# keg-vol-weight-mon.net
KiCad netlist of a schematic drawn in EAGLE
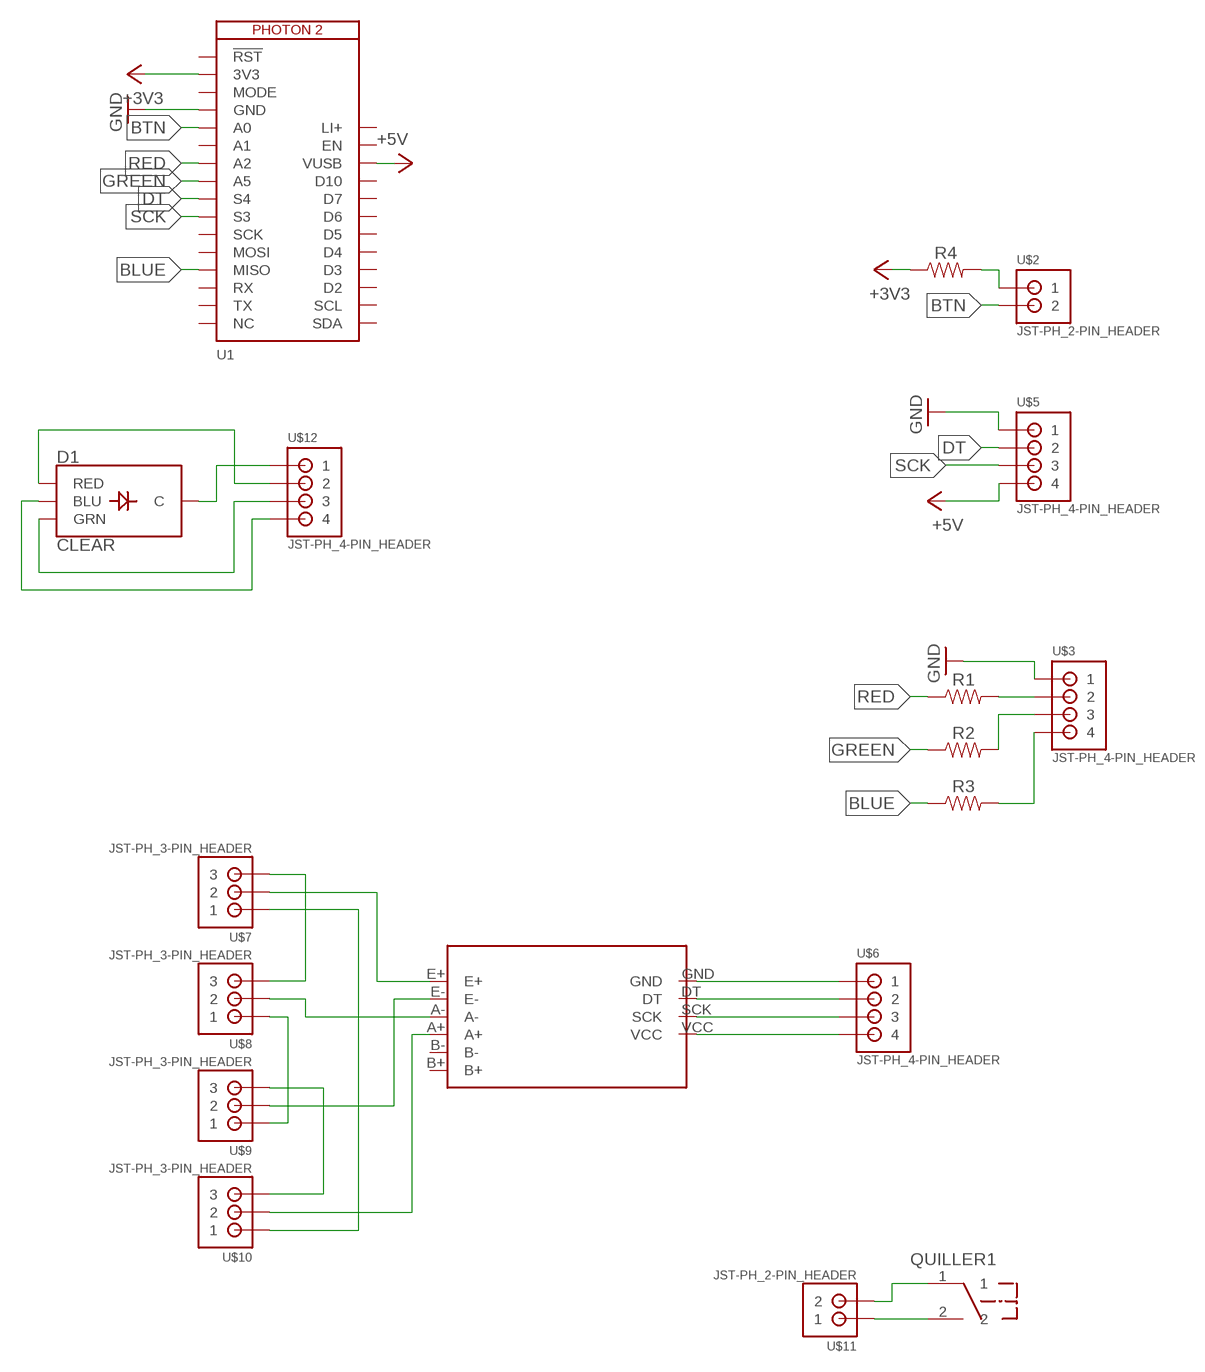
[diagram p0: schematic, sheet 1]

(export (version "E")
  (design (tool "Eeschema 10.0.6"))
  (components
    (comp (ref "D1")
      (value "CLEAR")
      (footprint "eagle-import:LED-RGB-THRU")
      (libsource (lib "eagle-import") (part "LED-RGB-CCCLEAR"))
    )
    (comp (ref "QUILLER1")
      (value "6MM-2PIN-TAC-MOM-SWITCH")
      (footprint "eagle-import:6MM-2PIN-TAC-MOM-SWITCH")
      (libsource (lib "eagle-import") (part "6MM-2PIN-TAC-MOM-SWITCH"))
    )
    (comp (ref "R1")
      (value "RESISTORAXIAL-0.3")
      (footprint "eagle-import:AXIAL-0.3")
      (libsource (lib "eagle-import") (part "RESISTORAXIAL-0.3"))
    )
    (comp (ref "R2")
      (value "RESISTORAXIAL-0.3")
      (footprint "eagle-import:AXIAL-0.3")
      (libsource (lib "eagle-import") (part "RESISTORAXIAL-0.3"))
    )
    (comp (ref "R3")
      (value "RESISTORAXIAL-0.3")
      (footprint "eagle-import:AXIAL-0.3")
      (libsource (lib "eagle-import") (part "RESISTORAXIAL-0.3"))
    )
    (comp (ref "R4")
      (value "RESISTORAXIAL-0.3")
      (footprint "eagle-import:AXIAL-0.3")
      (libsource (lib "eagle-import") (part "RESISTORAXIAL-0.3"))
    )
    (comp (ref "U$2")
      (value "JST-PH_2-PIN_HEADER")
      (footprint "eagle-import:JST_B2B-PH_HEADER")
      (libsource (lib "eagle-import") (part "JST-PH_2-PIN_HEADER"))
    )
    (comp (ref "U$3")
      (value "JST-PH_4-PIN_HEADER")
      (footprint "eagle-import:JST_B4B-PH_HEADER")
      (libsource (lib "eagle-import") (part "JST-PH_4-PIN_HEADER"))
    )
    (comp (ref "U$4")
      (value "HX711A")
      (footprint "eagle-import:HX711")
      (libsource (lib "eagle-import") (part "HX711A"))
    )
    (comp (ref "U$5")
      (value "JST-PH_4-PIN_HEADER")
      (footprint "eagle-import:JST_B4B-PH_HEADER")
      (libsource (lib "eagle-import") (part "JST-PH_4-PIN_HEADER"))
    )
    (comp (ref "U$6")
      (value "JST-PH_4-PIN_HEADER")
      (footprint "eagle-import:JST_B4B-PH_HEADER")
      (libsource (lib "eagle-import") (part "JST-PH_4-PIN_HEADER"))
    )
    (comp (ref "U$7")
      (value "JST-PH_3-PIN_HEADER")
      (footprint "eagle-import:JST_B3B-PH_HEADER")
      (libsource (lib "eagle-import") (part "JST-PH_3-PIN_HEADER"))
    )
    (comp (ref "U$8")
      (value "JST-PH_3-PIN_HEADER")
      (footprint "eagle-import:JST_B3B-PH_HEADER")
      (libsource (lib "eagle-import") (part "JST-PH_3-PIN_HEADER"))
    )
    (comp (ref "U$9")
      (value "JST-PH_3-PIN_HEADER")
      (footprint "eagle-import:JST_B3B-PH_HEADER")
      (libsource (lib "eagle-import") (part "JST-PH_3-PIN_HEADER"))
    )
    (comp (ref "U$10")
      (value "JST-PH_3-PIN_HEADER")
      (footprint "eagle-import:JST_B3B-PH_HEADER")
      (libsource (lib "eagle-import") (part "JST-PH_3-PIN_HEADER"))
    )
    (comp (ref "U$11")
      (value "JST-PH_2-PIN_HEADER")
      (footprint "eagle-import:JST_B2B-PH_HEADER")
      (libsource (lib "eagle-import") (part "JST-PH_2-PIN_HEADER"))
    )
    (comp (ref "U$12")
      (value "JST-PH_4-PIN_HEADER")
      (footprint "eagle-import:JST_B4B-PH_HEADER")
      (libsource (lib "eagle-import") (part "JST-PH_4-PIN_HEADER"))
    )
    (comp (ref "U1")
      (value "PHOTON2")
      (footprint "eagle-import:PHOTON2")
      (libsource (lib "eagle-import") (part "PHOTON2"))
    )
  )
  (nets
    (net (code "1") (name "+3V3") (class "Default")
      (node (ref "R4") (pin "P$1") (pinfunction "1_P$1") (pintype "passive"))
      (node (ref "U1") (pin "2") (pinfunction "3V3_2") (pintype "power_in"))
    )
    (net (code "2") (name "+5V") (class "Default")
      (node (ref "U$5") (pin "P4") (pinfunction "4_P4") (pintype "bidirectional"))
      (node (ref "U1") (pin "26") (pinfunction "VUSB_26") (pintype "power_in"))
    )
    (net (code "3") (name "/LI+") (class "Default")
      (node (ref "U1") (pin "28") (pinfunction "LI+_28") (pintype "power_in"))
    )
    (net (code "4") (name "BLUE") (class "Default")
      (node (ref "R3") (pin "P$1") (pinfunction "1_P$1") (pintype "passive"))
      (node (ref "U1") (pin "13") (pinfunction "MISO_13") (pintype "bidirectional"))
    )
    (net (code "5") (name "BTN") (class "Default")
      (node (ref "U$2") (pin "P2") (pinfunction "2_P2") (pintype "bidirectional"))
      (node (ref "U1") (pin "5") (pinfunction "A0_5") (pintype "bidirectional"))
    )
    (net (code "6") (name "DT") (class "Default")
      (node (ref "U$5") (pin "P2") (pinfunction "2_P2") (pintype "bidirectional"))
      (node (ref "U1") (pin "9") (pinfunction "S4_9") (pintype "bidirectional"))
    )
    (net (code "7") (name "GND") (class "Default")
      (node (ref "U$3") (pin "P1") (pinfunction "1_P1") (pintype "bidirectional"))
      (node (ref "U$5") (pin "P1") (pinfunction "1_P1") (pintype "bidirectional"))
      (node (ref "U1") (pin "4") (pinfunction "GND_4") (pintype "power_in"))
    )
    (net (code "8") (name "GREEN") (class "Default")
      (node (ref "R2") (pin "P$1") (pinfunction "1_P$1") (pintype "passive"))
      (node (ref "U1") (pin "8") (pinfunction "A5_8") (pintype "bidirectional"))
    )
    (net (code "9") (name "Net-(D1-BLU)") (class "Default")
      (node (ref "D1") (pin "4") (pinfunction "BLU_4") (pintype "bidirectional"))
      (node (ref "U$12") (pin "P4") (pinfunction "4_P4") (pintype "bidirectional"))
    )
    (net (code "10") (name "Net-(D1-C)") (class "Default")
      (node (ref "D1") (pin "2") (pinfunction "C_2") (pintype "bidirectional"))
      (node (ref "U$12") (pin "P1") (pinfunction "1_P1") (pintype "bidirectional"))
    )
    (net (code "11") (name "Net-(D1-GRN)") (class "Default")
      (node (ref "D1") (pin "3") (pinfunction "GRN_3") (pintype "bidirectional"))
      (node (ref "U$12") (pin "P3") (pinfunction "3_P3") (pintype "bidirectional"))
    )
    (net (code "12") (name "Net-(D1-RED)") (class "Default")
      (node (ref "D1") (pin "1") (pinfunction "RED_1") (pintype "bidirectional"))
      (node (ref "U$12") (pin "P2") (pinfunction "2_P2") (pintype "bidirectional"))
    )
    (net (code "13") (name "Net-(R1-2)") (class "Default")
      (node (ref "R1") (pin "P$2") (pinfunction "2_P$2") (pintype "passive"))
      (node (ref "U$3") (pin "P2") (pinfunction "2_P2") (pintype "bidirectional"))
    )
    (net (code "14") (name "Net-(R2-2)") (class "Default")
      (node (ref "R2") (pin "P$2") (pinfunction "2_P$2") (pintype "passive"))
      (node (ref "U$3") (pin "P3") (pinfunction "3_P3") (pintype "bidirectional"))
    )
    (net (code "15") (name "Net-(R3-2)") (class "Default")
      (node (ref "R3") (pin "P$2") (pinfunction "2_P$2") (pintype "passive"))
      (node (ref "U$3") (pin "P4") (pinfunction "4_P4") (pintype "bidirectional"))
    )
    (net (code "16") (name "Net-(R4-2)") (class "Default")
      (node (ref "R4") (pin "P$2") (pinfunction "2_P$2") (pintype "passive"))
      (node (ref "U$2") (pin "P1") (pinfunction "1_P1") (pintype "bidirectional"))
    )
    (net (code "17") (name "Net-(U$6-1)") (class "Default")
      (node (ref "U$4") (pin "GND") (pinfunction "GND_GND") (pintype "bidirectional"))
      (node (ref "U$6") (pin "P1") (pinfunction "1_P1") (pintype "bidirectional"))
    )
    (net (code "18") (name "Net-(U$6-2)") (class "Default")
      (node (ref "U$4") (pin "DT") (pinfunction "DT_DT") (pintype "bidirectional"))
      (node (ref "U$6") (pin "P2") (pinfunction "2_P2") (pintype "bidirectional"))
    )
    (net (code "19") (name "Net-(U$6-3)") (class "Default")
      (node (ref "U$4") (pin "SCK") (pinfunction "SCK_SCK") (pintype "bidirectional"))
      (node (ref "U$6") (pin "P3") (pinfunction "3_P3") (pintype "bidirectional"))
    )
    (net (code "20") (name "Net-(U$6-4)") (class "Default")
      (node (ref "U$4") (pin "VCC") (pinfunction "VCC_VCC") (pintype "bidirectional"))
      (node (ref "U$6") (pin "P4") (pinfunction "4_P4") (pintype "bidirectional"))
    )
    (net (code "21") (name "Net-(U$7-2)") (class "Default")
      (node (ref "U$4") (pin "E+") (pinfunction "E+_E+") (pintype "bidirectional"))
      (node (ref "U$7") (pin "P2") (pinfunction "2_P2") (pintype "bidirectional"))
    )
    (net (code "22") (name "Net-(U$7-3)") (class "Default")
      (node (ref "U$7") (pin "P3") (pinfunction "3_P3") (pintype "bidirectional"))
      (node (ref "U$8") (pin "P3") (pinfunction "3_P3") (pintype "bidirectional"))
    )
    (net (code "23") (name "Net-(U$8-1)") (class "Default")
      (node (ref "U$8") (pin "P1") (pinfunction "1_P1") (pintype "bidirectional"))
      (node (ref "U$9") (pin "P1") (pinfunction "1_P1") (pintype "bidirectional"))
    )
    (net (code "24") (name "Net-(U$8-2)") (class "Default")
      (node (ref "U$4") (pin "A-") (pinfunction "A-_A-") (pintype "bidirectional"))
      (node (ref "U$8") (pin "P2") (pinfunction "2_P2") (pintype "bidirectional"))
    )
    (net (code "25") (name "Net-(U$9-2)") (class "Default")
      (node (ref "U$4") (pin "E-") (pinfunction "E-_E-") (pintype "bidirectional"))
      (node (ref "U$9") (pin "P2") (pinfunction "2_P2") (pintype "bidirectional"))
    )
    (net (code "26") (name "Net-(U$10-1)") (class "Default")
      (node (ref "U$10") (pin "P1") (pinfunction "1_P1") (pintype "bidirectional"))
      (node (ref "U$7") (pin "P1") (pinfunction "1_P1") (pintype "bidirectional"))
    )
    (net (code "27") (name "Net-(U$10-2)") (class "Default")
      (node (ref "U$10") (pin "P2") (pinfunction "2_P2") (pintype "bidirectional"))
      (node (ref "U$4") (pin "A+") (pinfunction "A+_A+") (pintype "bidirectional"))
    )
    (net (code "28") (name "Net-(U$10-3)") (class "Default")
      (node (ref "U$10") (pin "P3") (pinfunction "3_P3") (pintype "bidirectional"))
      (node (ref "U$9") (pin "P3") (pinfunction "3_P3") (pintype "bidirectional"))
    )
    (net (code "29") (name "Net-(U$11-1)") (class "Default")
      (node (ref "QUILLER1") (pin "2") (pinfunction "2_2") (pintype "bidirectional"))
      (node (ref "U$11") (pin "P1") (pinfunction "1_P1") (pintype "bidirectional"))
    )
    (net (code "30") (name "Net-(U$11-2)") (class "Default")
      (node (ref "QUILLER1") (pin "1") (pinfunction "1_1") (pintype "bidirectional"))
      (node (ref "U$11") (pin "P2") (pinfunction "2_P2") (pintype "bidirectional"))
    )
    (net (code "31") (name "RED") (class "Default")
      (node (ref "R1") (pin "P$1") (pinfunction "1_P$1") (pintype "passive"))
      (node (ref "U1") (pin "7") (pinfunction "A2_7") (pintype "bidirectional"))
    )
    (net (code "32") (name "SCK") (class "Default")
      (node (ref "U$5") (pin "P3") (pinfunction "3_P3") (pintype "bidirectional"))
      (node (ref "U1") (pin "10") (pinfunction "S3_10") (pintype "bidirectional"))
    )
    (net (code "33") (name "unconnected-(U$4-PadB+)") (class "Default")
      (node (ref "U$4") (pin "B+") (pinfunction "B+_B+") (pintype "bidirectional"))
    )
    (net (code "34") (name "unconnected-(U$4-PadB-)") (class "Default")
      (node (ref "U$4") (pin "B-") (pinfunction "B-_B-") (pintype "bidirectional"))
    )
    (net (code "35") (name "unconnected-(U1-A1-Pad6)") (class "Default")
      (node (ref "U1") (pin "6") (pinfunction "A1_6") (pintype "bidirectional"))
    )
    (net (code "36") (name "unconnected-(U1-D2-Pad19)") (class "Default")
      (node (ref "U1") (pin "19") (pinfunction "D2_19") (pintype "bidirectional"))
    )
    (net (code "37") (name "unconnected-(U1-D3-Pad20)") (class "Default")
      (node (ref "U1") (pin "20") (pinfunction "D3_20") (pintype "bidirectional"))
    )
    (net (code "38") (name "unconnected-(U1-D4-Pad21)") (class "Default")
      (node (ref "U1") (pin "21") (pinfunction "D4_21") (pintype "bidirectional"))
    )
    (net (code "39") (name "unconnected-(U1-D5-Pad22)") (class "Default")
      (node (ref "U1") (pin "22") (pinfunction "D5_22") (pintype "bidirectional"))
    )
    (net (code "40") (name "unconnected-(U1-D6-Pad23)") (class "Default")
      (node (ref "U1") (pin "23") (pinfunction "D6_23") (pintype "bidirectional"))
    )
    (net (code "41") (name "unconnected-(U1-D7-Pad24)") (class "Default")
      (node (ref "U1") (pin "24") (pinfunction "D7_24") (pintype "bidirectional"))
    )
    (net (code "42") (name "unconnected-(U1-D10-Pad25)") (class "Default")
      (node (ref "U1") (pin "25") (pinfunction "D10_25") (pintype "bidirectional"))
    )
    (net (code "43") (name "unconnected-(U1-EN-Pad27)") (class "Default")
      (node (ref "U1") (pin "27") (pinfunction "EN_27") (pintype "input"))
    )
    (net (code "44") (name "unconnected-(U1-MODE-Pad3)") (class "Default")
      (node (ref "U1") (pin "3") (pinfunction "MODE_3") (pintype "bidirectional"))
    )
    (net (code "45") (name "unconnected-(U1-MOSI-Pad12)") (class "Default")
      (node (ref "U1") (pin "12") (pinfunction "MOSI_12") (pintype "bidirectional"))
    )
    (net (code "46") (name "unconnected-(U1-NC-Pad16)") (class "Default")
      (node (ref "U1") (pin "16") (pinfunction "NC_16") (pintype "bidirectional"))
    )
    (net (code "47") (name "unconnected-(U1-RX-Pad14)") (class "Default")
      (node (ref "U1") (pin "14") (pinfunction "RX_14") (pintype "bidirectional"))
    )
    (net (code "48") (name "unconnected-(U1-SCK-Pad11)") (class "Default")
      (node (ref "U1") (pin "11") (pinfunction "SCK_11") (pintype "bidirectional"))
    )
    (net (code "49") (name "unconnected-(U1-SCL-Pad18)") (class "Default")
      (node (ref "U1") (pin "18") (pinfunction "SCL_18") (pintype "bidirectional"))
    )
    (net (code "50") (name "unconnected-(U1-SDA-Pad17)") (class "Default")
      (node (ref "U1") (pin "17") (pinfunction "SDA_17") (pintype "bidirectional"))
    )
    (net (code "51") (name "unconnected-(U1-TX-Pad15)") (class "Default")
      (node (ref "U1") (pin "15") (pinfunction "TX_15") (pintype "bidirectional"))
    )
    (net (code "52") (name "unconnected-(U1-~{RST}-Pad1)") (class "Default")
      (node (ref "U1") (pin "1") (pinfunction "~{RST}_1") (pintype "input"))
    )
  )
)
